# total_universal.net
KiCad netlist of a schematic drawn in EAGLE
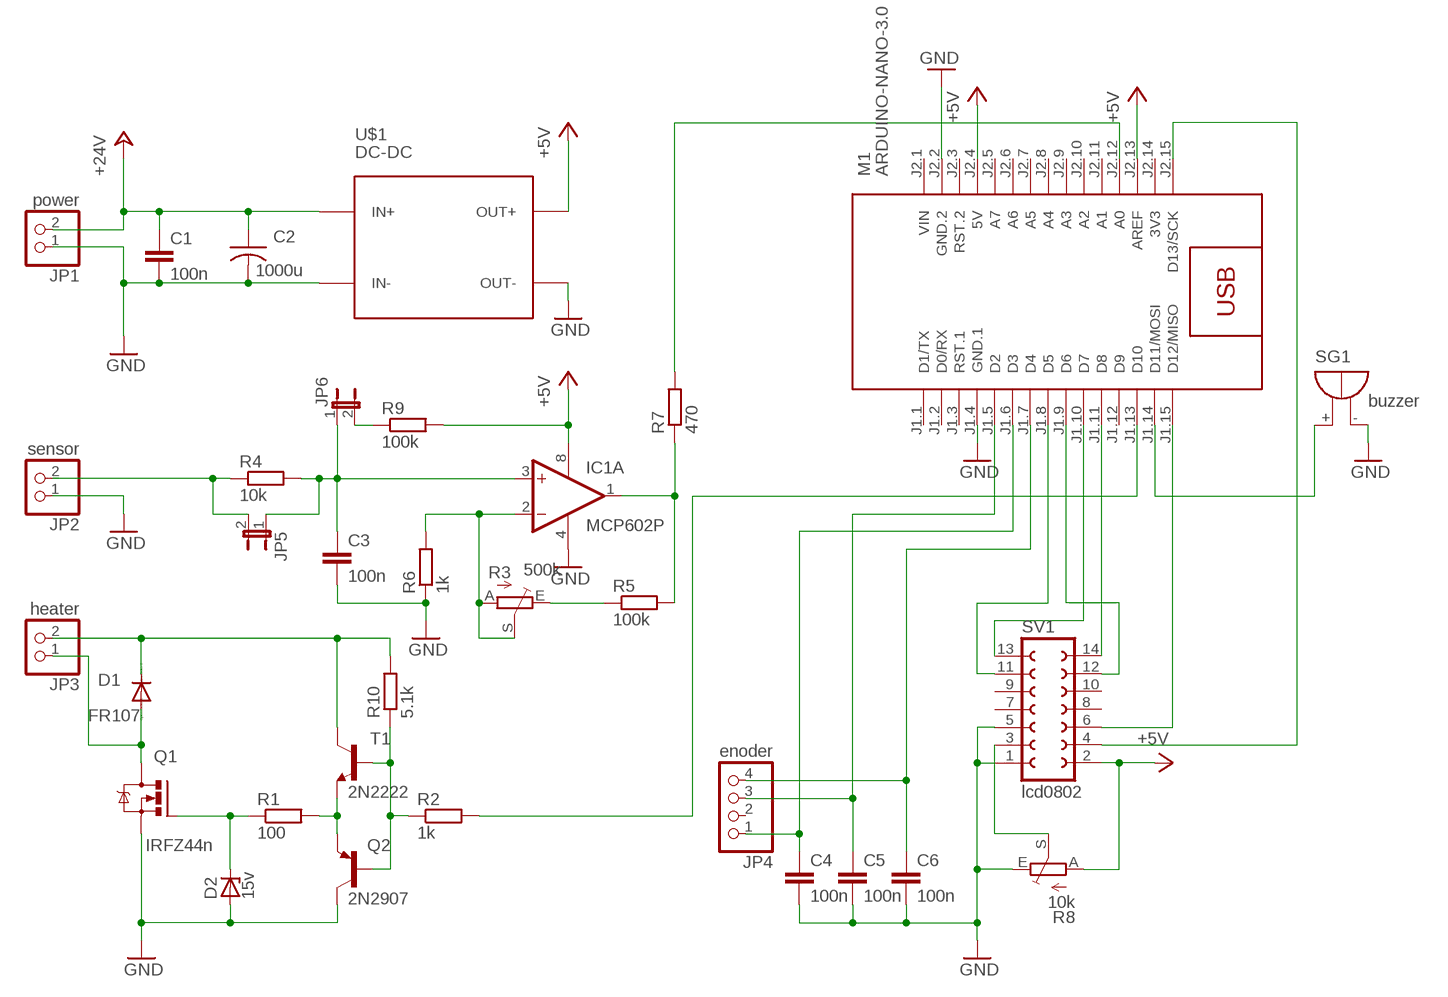
[diagram p0: schematic, sheet 1]

(export (version "E")
  (design (tool "Eeschema 10.0.6"))
  (components
    (comp (ref "C1")
      (value "100n")
      (footprint "eagle-import:C025-025X050")
      (libsource (lib "eagle-import") (part "C-EU025-025X050"))
    )
    (comp (ref "C2")
      (value "1000u")
      (footprint "eagle-import:C025-025X050")
      (libsource (lib "eagle-import") (part "C-US025-025X050"))
    )
    (comp (ref "C3")
      (value "100n")
      (footprint "eagle-import:C025-025X050")
      (libsource (lib "eagle-import") (part "C-EU025-025X050"))
    )
    (comp (ref "C4")
      (value "100n")
      (footprint "eagle-import:C025-025X050")
      (libsource (lib "eagle-import") (part "C-EU025-025X050"))
    )
    (comp (ref "C5")
      (value "100n")
      (footprint "eagle-import:C025-025X050")
      (libsource (lib "eagle-import") (part "C-EU025-025X050"))
    )
    (comp (ref "C6")
      (value "100n")
      (footprint "eagle-import:C025-025X050")
      (libsource (lib "eagle-import") (part "C-EU025-025X050"))
    )
    (comp (ref "D1")
      (value "FR107")
      (footprint "eagle-import:DO41-10")
      (libsource (lib "eagle-import") (part "1N4004"))
    )
    (comp (ref "D2")
      (value "15v")
      (footprint "eagle-import:C1702-15")
      (libsource (lib "eagle-import") (part "ZENER-DIODEC1702-15"))
    )
    (comp (ref "IC1")
      (value "MCP602P")
      (footprint "eagle-import:DIL08")
      (libsource (lib "eagle-import") (part "MCP602P"))
    )
    (comp (ref "JP1")
      (value "power")
      (footprint "eagle-import:1X02")
      (libsource (lib "eagle-import") (part "PINHD-1X2"))
    )
    (comp (ref "JP2")
      (value "sensor")
      (footprint "eagle-import:1X02")
      (libsource (lib "eagle-import") (part "PINHD-1X2"))
    )
    (comp (ref "JP3")
      (value "heater")
      (footprint "eagle-import:1X02")
      (libsource (lib "eagle-import") (part "PINHD-1X2"))
    )
    (comp (ref "JP4")
      (value "enoder")
      (footprint "eagle-import:1X04")
      (libsource (lib "eagle-import") (part "PINHD-1X4"))
    )
    (comp (ref "JP5")
      (value "JP1E")
      (footprint "eagle-import:JP1")
      (libsource (lib "eagle-import") (part "JP1E"))
    )
    (comp (ref "JP6")
      (value "JP1E")
      (footprint "eagle-import:JP1")
      (libsource (lib "eagle-import") (part "JP1E"))
    )
    (comp (ref "M1")
      (value "ARDUINO-NANO-3.0")
      (footprint "eagle-import:ARDUINO-NANO-3.0")
      (libsource (lib "eagle-import") (part "ARDUINO-NANO-3.0"))
    )
    (comp (ref "Q1")
      (value "IRFZ44n")
      (footprint "eagle-import:TO220BH")
      (libsource (lib "eagle-import") (part "IRLZ44Z"))
    )
    (comp (ref "Q2")
      (value "2N2907")
      (footprint "eagle-import:TO5")
      (libsource (lib "eagle-import") (part "2N2905"))
    )
    (comp (ref "R1")
      (value "100")
      (footprint "eagle-import:0204_5")
      (libsource (lib "eagle-import") (part "R-EU_0204/5"))
    )
    (comp (ref "R2")
      (value "1k")
      (footprint "eagle-import:0204_5")
      (libsource (lib "eagle-import") (part "R-EU_0204/5"))
    )
    (comp (ref "R3")
      (value "500k")
      (footprint "eagle-import:B64Y")
      (libsource (lib "eagle-import") (part "TRIM_EU-B64Y"))
    )
    (comp (ref "R4")
      (value "10k")
      (footprint "eagle-import:0204_5")
      (libsource (lib "eagle-import") (part "R-EU_0204/5"))
    )
    (comp (ref "R5")
      (value "100k")
      (footprint "eagle-import:0204_5")
      (libsource (lib "eagle-import") (part "R-EU_0204/5"))
    )
    (comp (ref "R6")
      (value "1k")
      (footprint "eagle-import:0204_5")
      (libsource (lib "eagle-import") (part "R-EU_0204/5"))
    )
    (comp (ref "R7")
      (value "470")
      (footprint "eagle-import:0204_5")
      (libsource (lib "eagle-import") (part "R-EU_0204/5"))
    )
    (comp (ref "R8")
      (value "10k")
      (footprint "eagle-import:B64Y")
      (libsource (lib "eagle-import") (part "TRIM_EU-B64Y"))
    )
    (comp (ref "R9")
      (value "100k")
      (footprint "eagle-import:0204_5")
      (libsource (lib "eagle-import") (part "R-EU_0204/5"))
    )
    (comp (ref "R10")
      (value "5.1k")
      (footprint "eagle-import:0204_5")
      (libsource (lib "eagle-import") (part "R-EU_0204/5"))
    )
    (comp (ref "SG1")
      (value "buzzer")
      (footprint "eagle-import:EB2209A")
      (libsource (lib "eagle-import") (part "EB2209A"))
    )
    (comp (ref "SV1")
      (value "lcd0802")
      (footprint "eagle-import:FE07-2")
      (libsource (lib "eagle-import") (part "FE07-2"))
    )
    (comp (ref "T1")
      (value "2N2222")
      (footprint "eagle-import:TO18")
      (libsource (lib "eagle-import") (part "2N2222"))
    )
    (comp (ref "U$1")
      (value "DC-DC")
      (footprint "eagle-import:DC-DC-STEP-DOWN-LM2596")
      (libsource (lib "eagle-import") (part "DC-DC-STEP-DOWN-LM2596"))
    )
  )
  (nets
    (net (code "1") (name "+5V") (class "Default")
      (node (ref "IC1") (pin "8") (pinfunction "V+_8") (pintype "power_in"))
      (node (ref "M1") (pin "J2.13") (pinfunction "AREF_J2.13") (pintype "bidirectional"))
      (node (ref "M1") (pin "J2.4") (pinfunction "5V_J2.4") (pintype "power_in"))
      (node (ref "R8") (pin "A") (pinfunction "A_A") (pintype "passive"))
      (node (ref "R9") (pin "2") (pinfunction "2_2") (pintype "passive"))
      (node (ref "SV1") (pin "2") (pinfunction "2_2") (pintype "passive"))
      (node (ref "U$1") (pin "OUT+") (pinfunction "OUT+_OUT+") (pintype "bidirectional"))
    )
    (net (code "2") (name "+24V") (class "Default")
      (node (ref "C1") (pin "1") (pinfunction "1_1") (pintype "passive"))
      (node (ref "C2") (pin "1") (pinfunction "1_1") (pintype "passive"))
      (node (ref "JP1") (pin "2") (pinfunction "2_2") (pintype "passive"))
      (node (ref "U$1") (pin "IN+") (pinfunction "IN+_IN+") (pintype "bidirectional"))
    )
    (net (code "3") (name "/3V3") (class "Default")
      (node (ref "M1") (pin "J2.14") (pinfunction "3V3_J2.14") (pintype "power_in"))
    )
    (net (code "4") (name "/VIN") (class "Default")
      (node (ref "M1") (pin "J2.1") (pinfunction "VIN_J2.1") (pintype "power_in"))
    )
    (net (code "5") (name "GND") (class "Default")
      (node (ref "C1") (pin "2") (pinfunction "2_2") (pintype "passive"))
      (node (ref "C2") (pin "2") (pinfunction "2_2") (pintype "passive"))
      (node (ref "C3") (pin "2") (pinfunction "2_2") (pintype "passive"))
      (node (ref "C4") (pin "2") (pinfunction "2_2") (pintype "passive"))
      (node (ref "C5") (pin "2") (pinfunction "2_2") (pintype "passive"))
      (node (ref "C6") (pin "2") (pinfunction "2_2") (pintype "passive"))
      (node (ref "D2") (pin "A") (pinfunction "A_A") (pintype "passive"))
      (node (ref "IC1") (pin "4") (pinfunction "V-_4") (pintype "power_in"))
      (node (ref "JP1") (pin "1") (pinfunction "1_1") (pintype "passive"))
      (node (ref "JP2") (pin "1") (pinfunction "1_1") (pintype "passive"))
      (node (ref "M1") (pin "J1.4") (pinfunction "GND.1_J1.4") (pintype "power_in"))
      (node (ref "M1") (pin "J2.2") (pinfunction "GND.2_J2.2") (pintype "power_in"))
      (node (ref "Q1") (pin "S") (pinfunction "S_S") (pintype "passive"))
      (node (ref "Q2") (pin "3") (pinfunction "C_3") (pintype "passive"))
      (node (ref "R6") (pin "1") (pinfunction "1_1") (pintype "passive"))
      (node (ref "R8") (pin "E") (pinfunction "E_E") (pintype "passive"))
      (node (ref "SG1") (pin "-") (pinfunction "-_-") (pintype "passive"))
      (node (ref "SV1") (pin "1") (pinfunction "1_1") (pintype "passive"))
      (node (ref "SV1") (pin "5") (pinfunction "5_5") (pintype "passive"))
      (node (ref "U$1") (pin "IN-") (pinfunction "IN-_IN-") (pintype "bidirectional"))
      (node (ref "U$1") (pin "OUT-") (pinfunction "OUT-_OUT-") (pintype "bidirectional"))
    )
    (net (code "6") (name "Net-(D1-PadA)") (class "Default")
      (node (ref "D1") (pin "A") (pinfunction "A_A") (pintype "passive"))
      (node (ref "JP3") (pin "1") (pinfunction "1_1") (pintype "passive"))
      (node (ref "Q1") (pin "D") (pinfunction "D_D") (pintype "passive"))
    )
    (net (code "7") (name "Net-(D2-PadC)") (class "Default")
      (node (ref "D2") (pin "C") (pinfunction "C_C") (pintype "passive"))
      (node (ref "Q1") (pin "G") (pinfunction "G_G") (pintype "passive"))
      (node (ref "R1") (pin "1") (pinfunction "1_1") (pintype "passive"))
    )
    (net (code "8") (name "Net-(IC1A-+IN)") (class "Default")
      (node (ref "C3") (pin "1") (pinfunction "1_1") (pintype "passive"))
      (node (ref "IC1") (pin "3") (pinfunction "+IN_3") (pintype "input"))
      (node (ref "JP5") (pin "1") (pinfunction "1_1") (pintype "passive"))
      (node (ref "JP6") (pin "1") (pinfunction "1_1") (pintype "passive"))
      (node (ref "R4") (pin "2") (pinfunction "2_2") (pintype "passive"))
    )
    (net (code "9") (name "Net-(IC1A--IN)") (class "Default")
      (node (ref "IC1") (pin "2") (pinfunction "-IN_2") (pintype "input"))
      (node (ref "R3") (pin "A") (pinfunction "A_A") (pintype "passive"))
      (node (ref "R3") (pin "S") (pinfunction "S_S") (pintype "passive"))
      (node (ref "R6") (pin "2") (pinfunction "2_2") (pintype "passive"))
    )
    (net (code "10") (name "Net-(IC1A-OUT)") (class "Default")
      (node (ref "IC1") (pin "1") (pinfunction "OUT_1") (pintype "output"))
      (node (ref "R5") (pin "2") (pinfunction "2_2") (pintype "passive"))
      (node (ref "R7") (pin "1") (pinfunction "1_1") (pintype "passive"))
    )
    (net (code "11") (name "Net-(JP2-Pad2)") (class "Default")
      (node (ref "JP2") (pin "2") (pinfunction "2_2") (pintype "passive"))
      (node (ref "JP5") (pin "2") (pinfunction "2_2") (pintype "passive"))
      (node (ref "R4") (pin "1") (pinfunction "1_1") (pintype "passive"))
    )
    (net (code "12") (name "Net-(JP6-Pad2)") (class "Default")
      (node (ref "JP6") (pin "2") (pinfunction "2_2") (pintype "passive"))
      (node (ref "R9") (pin "1") (pinfunction "1_1") (pintype "passive"))
    )
    (net (code "13") (name "Net-(M1-A0)") (class "Default")
      (node (ref "M1") (pin "J2.12") (pinfunction "A0_J2.12") (pintype "bidirectional"))
      (node (ref "R7") (pin "2") (pinfunction "2_2") (pintype "passive"))
    )
    (net (code "14") (name "Net-(M1-D2)") (class "Default")
      (node (ref "C5") (pin "1") (pinfunction "1_1") (pintype "passive"))
      (node (ref "JP4") (pin "3") (pinfunction "3_3") (pintype "passive"))
      (node (ref "M1") (pin "J1.5") (pinfunction "D2_J1.5") (pintype "bidirectional"))
    )
    (net (code "15") (name "Net-(M1-D3)") (class "Default")
      (node (ref "C4") (pin "1") (pinfunction "1_1") (pintype "passive"))
      (node (ref "JP4") (pin "1") (pinfunction "1_1") (pintype "passive"))
      (node (ref "M1") (pin "J1.6") (pinfunction "D3_J1.6") (pintype "bidirectional"))
    )
    (net (code "16") (name "Net-(M1-D4)") (class "Default")
      (node (ref "C6") (pin "1") (pinfunction "1_1") (pintype "passive"))
      (node (ref "JP4") (pin "4") (pinfunction "4_4") (pintype "passive"))
      (node (ref "M1") (pin "J1.7") (pinfunction "D4_J1.7") (pintype "bidirectional"))
    )
    (net (code "17") (name "Net-(M1-D5)") (class "Default")
      (node (ref "M1") (pin "J1.8") (pinfunction "D5_J1.8") (pintype "bidirectional"))
      (node (ref "SV1") (pin "11") (pinfunction "11_11") (pintype "passive"))
    )
    (net (code "18") (name "Net-(M1-D6)") (class "Default")
      (node (ref "M1") (pin "J1.9") (pinfunction "D6_J1.9") (pintype "bidirectional"))
      (node (ref "SV1") (pin "12") (pinfunction "12_12") (pintype "passive"))
    )
    (net (code "19") (name "Net-(M1-D7)") (class "Default")
      (node (ref "M1") (pin "J1.10") (pinfunction "D7_J1.10") (pintype "bidirectional"))
      (node (ref "SV1") (pin "13") (pinfunction "13_13") (pintype "passive"))
    )
    (net (code "20") (name "Net-(M1-D8)") (class "Default")
      (node (ref "M1") (pin "J1.11") (pinfunction "D8_J1.11") (pintype "bidirectional"))
      (node (ref "SV1") (pin "14") (pinfunction "14_14") (pintype "passive"))
    )
    (net (code "21") (name "Net-(M1-D10)") (class "Default")
      (node (ref "M1") (pin "J1.13") (pinfunction "D10_J1.13") (pintype "bidirectional"))
      (node (ref "R2") (pin "2") (pinfunction "2_2") (pintype "passive"))
    )
    (net (code "22") (name "Net-(M1-D11{slash}MOSI)") (class "Default")
      (node (ref "M1") (pin "J1.14") (pinfunction "D11/MOSI_J1.14") (pintype "bidirectional"))
      (node (ref "SG1") (pin "+") (pinfunction "+_+") (pintype "passive"))
    )
    (net (code "23") (name "Net-(M1-D12{slash}MISO)") (class "Default")
      (node (ref "M1") (pin "J1.15") (pinfunction "D12/MISO_J1.15") (pintype "bidirectional"))
      (node (ref "SV1") (pin "6") (pinfunction "6_6") (pintype "passive"))
    )
    (net (code "24") (name "Net-(M1-D13{slash}SCK)") (class "Default")
      (node (ref "M1") (pin "J2.15") (pinfunction "D13/SCK_J2.15") (pintype "bidirectional"))
      (node (ref "SV1") (pin "4") (pinfunction "4_4") (pintype "passive"))
    )
    (net (code "25") (name "Net-(Q2-B)") (class "Default")
      (node (ref "Q2") (pin "2") (pinfunction "B_2") (pintype "passive"))
      (node (ref "R10") (pin "1") (pinfunction "1_1") (pintype "passive"))
      (node (ref "R2") (pin "1") (pinfunction "1_1") (pintype "passive"))
      (node (ref "T1") (pin "2") (pinfunction "B_2") (pintype "passive"))
    )
    (net (code "26") (name "Net-(Q2-E)") (class "Default")
      (node (ref "Q2") (pin "1") (pinfunction "E_1") (pintype "passive"))
      (node (ref "R1") (pin "2") (pinfunction "2_2") (pintype "passive"))
      (node (ref "T1") (pin "1") (pinfunction "E_1") (pintype "passive"))
    )
    (net (code "27") (name "Net-(R3-PadE)") (class "Default")
      (node (ref "R3") (pin "E") (pinfunction "E_E") (pintype "passive"))
      (node (ref "R5") (pin "1") (pinfunction "1_1") (pintype "passive"))
    )
    (net (code "28") (name "Net-(R8-PadS)") (class "Default")
      (node (ref "R8") (pin "S") (pinfunction "S_S") (pintype "passive"))
      (node (ref "SV1") (pin "3") (pinfunction "3_3") (pintype "passive"))
    )
    (net (code "29") (name "Net-(T1-C)") (class "Default")
      (node (ref "D1") (pin "C") (pinfunction "C_C") (pintype "passive"))
      (node (ref "JP3") (pin "2") (pinfunction "2_2") (pintype "passive"))
      (node (ref "R10") (pin "2") (pinfunction "2_2") (pintype "passive"))
      (node (ref "T1") (pin "3") (pinfunction "C_3") (pintype "passive"))
    )
    (net (code "30") (name "unconnected-(JP4-Pad2)") (class "Default")
      (node (ref "JP4") (pin "2") (pinfunction "2_2") (pintype "passive"))
    )
    (net (code "31") (name "unconnected-(M1-A1-PadJ2.11)") (class "Default")
      (node (ref "M1") (pin "J2.11") (pinfunction "A1_J2.11") (pintype "bidirectional"))
    )
    (net (code "32") (name "unconnected-(M1-A2-PadJ2.10)") (class "Default")
      (node (ref "M1") (pin "J2.10") (pinfunction "A2_J2.10") (pintype "bidirectional"))
    )
    (net (code "33") (name "unconnected-(M1-A3-PadJ2.9)") (class "Default")
      (node (ref "M1") (pin "J2.9") (pinfunction "A3_J2.9") (pintype "bidirectional"))
    )
    (net (code "34") (name "unconnected-(M1-A4-PadJ2.8)") (class "Default")
      (node (ref "M1") (pin "J2.8") (pinfunction "A4_J2.8") (pintype "bidirectional"))
    )
    (net (code "35") (name "unconnected-(M1-A5-PadJ2.7)") (class "Default")
      (node (ref "M1") (pin "J2.7") (pinfunction "A5_J2.7") (pintype "bidirectional"))
    )
    (net (code "36") (name "unconnected-(M1-A6-PadJ2.6)") (class "Default")
      (node (ref "M1") (pin "J2.6") (pinfunction "A6_J2.6") (pintype "bidirectional"))
    )
    (net (code "37") (name "unconnected-(M1-A7-PadJ2.5)") (class "Default")
      (node (ref "M1") (pin "J2.5") (pinfunction "A7_J2.5") (pintype "bidirectional"))
    )
    (net (code "38") (name "unconnected-(M1-D0{slash}RX-PadJ1.2)") (class "Default")
      (node (ref "M1") (pin "J1.2") (pinfunction "D0/RX_J1.2") (pintype "bidirectional"))
    )
    (net (code "39") (name "unconnected-(M1-D1{slash}TX-PadJ1.1)") (class "Default")
      (node (ref "M1") (pin "J1.1") (pinfunction "D1/TX_J1.1") (pintype "bidirectional"))
    )
    (net (code "40") (name "unconnected-(M1-D9-PadJ1.12)") (class "Default")
      (node (ref "M1") (pin "J1.12") (pinfunction "D9_J1.12") (pintype "bidirectional"))
    )
    (net (code "41") (name "unconnected-(M1-RST.1-PadJ1.3)") (class "Default")
      (node (ref "M1") (pin "J1.3") (pinfunction "RST.1_J1.3") (pintype "bidirectional"))
    )
    (net (code "42") (name "unconnected-(M1-RST.2-PadJ2.3)") (class "Default")
      (node (ref "M1") (pin "J2.3") (pinfunction "RST.2_J2.3") (pintype "bidirectional"))
    )
    (net (code "43") (name "unconnected-(SV1-Pad7)") (class "Default")
      (node (ref "SV1") (pin "7") (pinfunction "7_7") (pintype "passive"))
    )
    (net (code "44") (name "unconnected-(SV1-Pad8)") (class "Default")
      (node (ref "SV1") (pin "8") (pinfunction "8_8") (pintype "passive"))
    )
    (net (code "45") (name "unconnected-(SV1-Pad9)") (class "Default")
      (node (ref "SV1") (pin "9") (pinfunction "9_9") (pintype "passive"))
    )
    (net (code "46") (name "unconnected-(SV1-Pad10)") (class "Default")
      (node (ref "SV1") (pin "10") (pinfunction "10_10") (pintype "passive"))
    )
  )
)
